# Grabber.net
KiCad netlist of a schematic drawn in Altium Designer
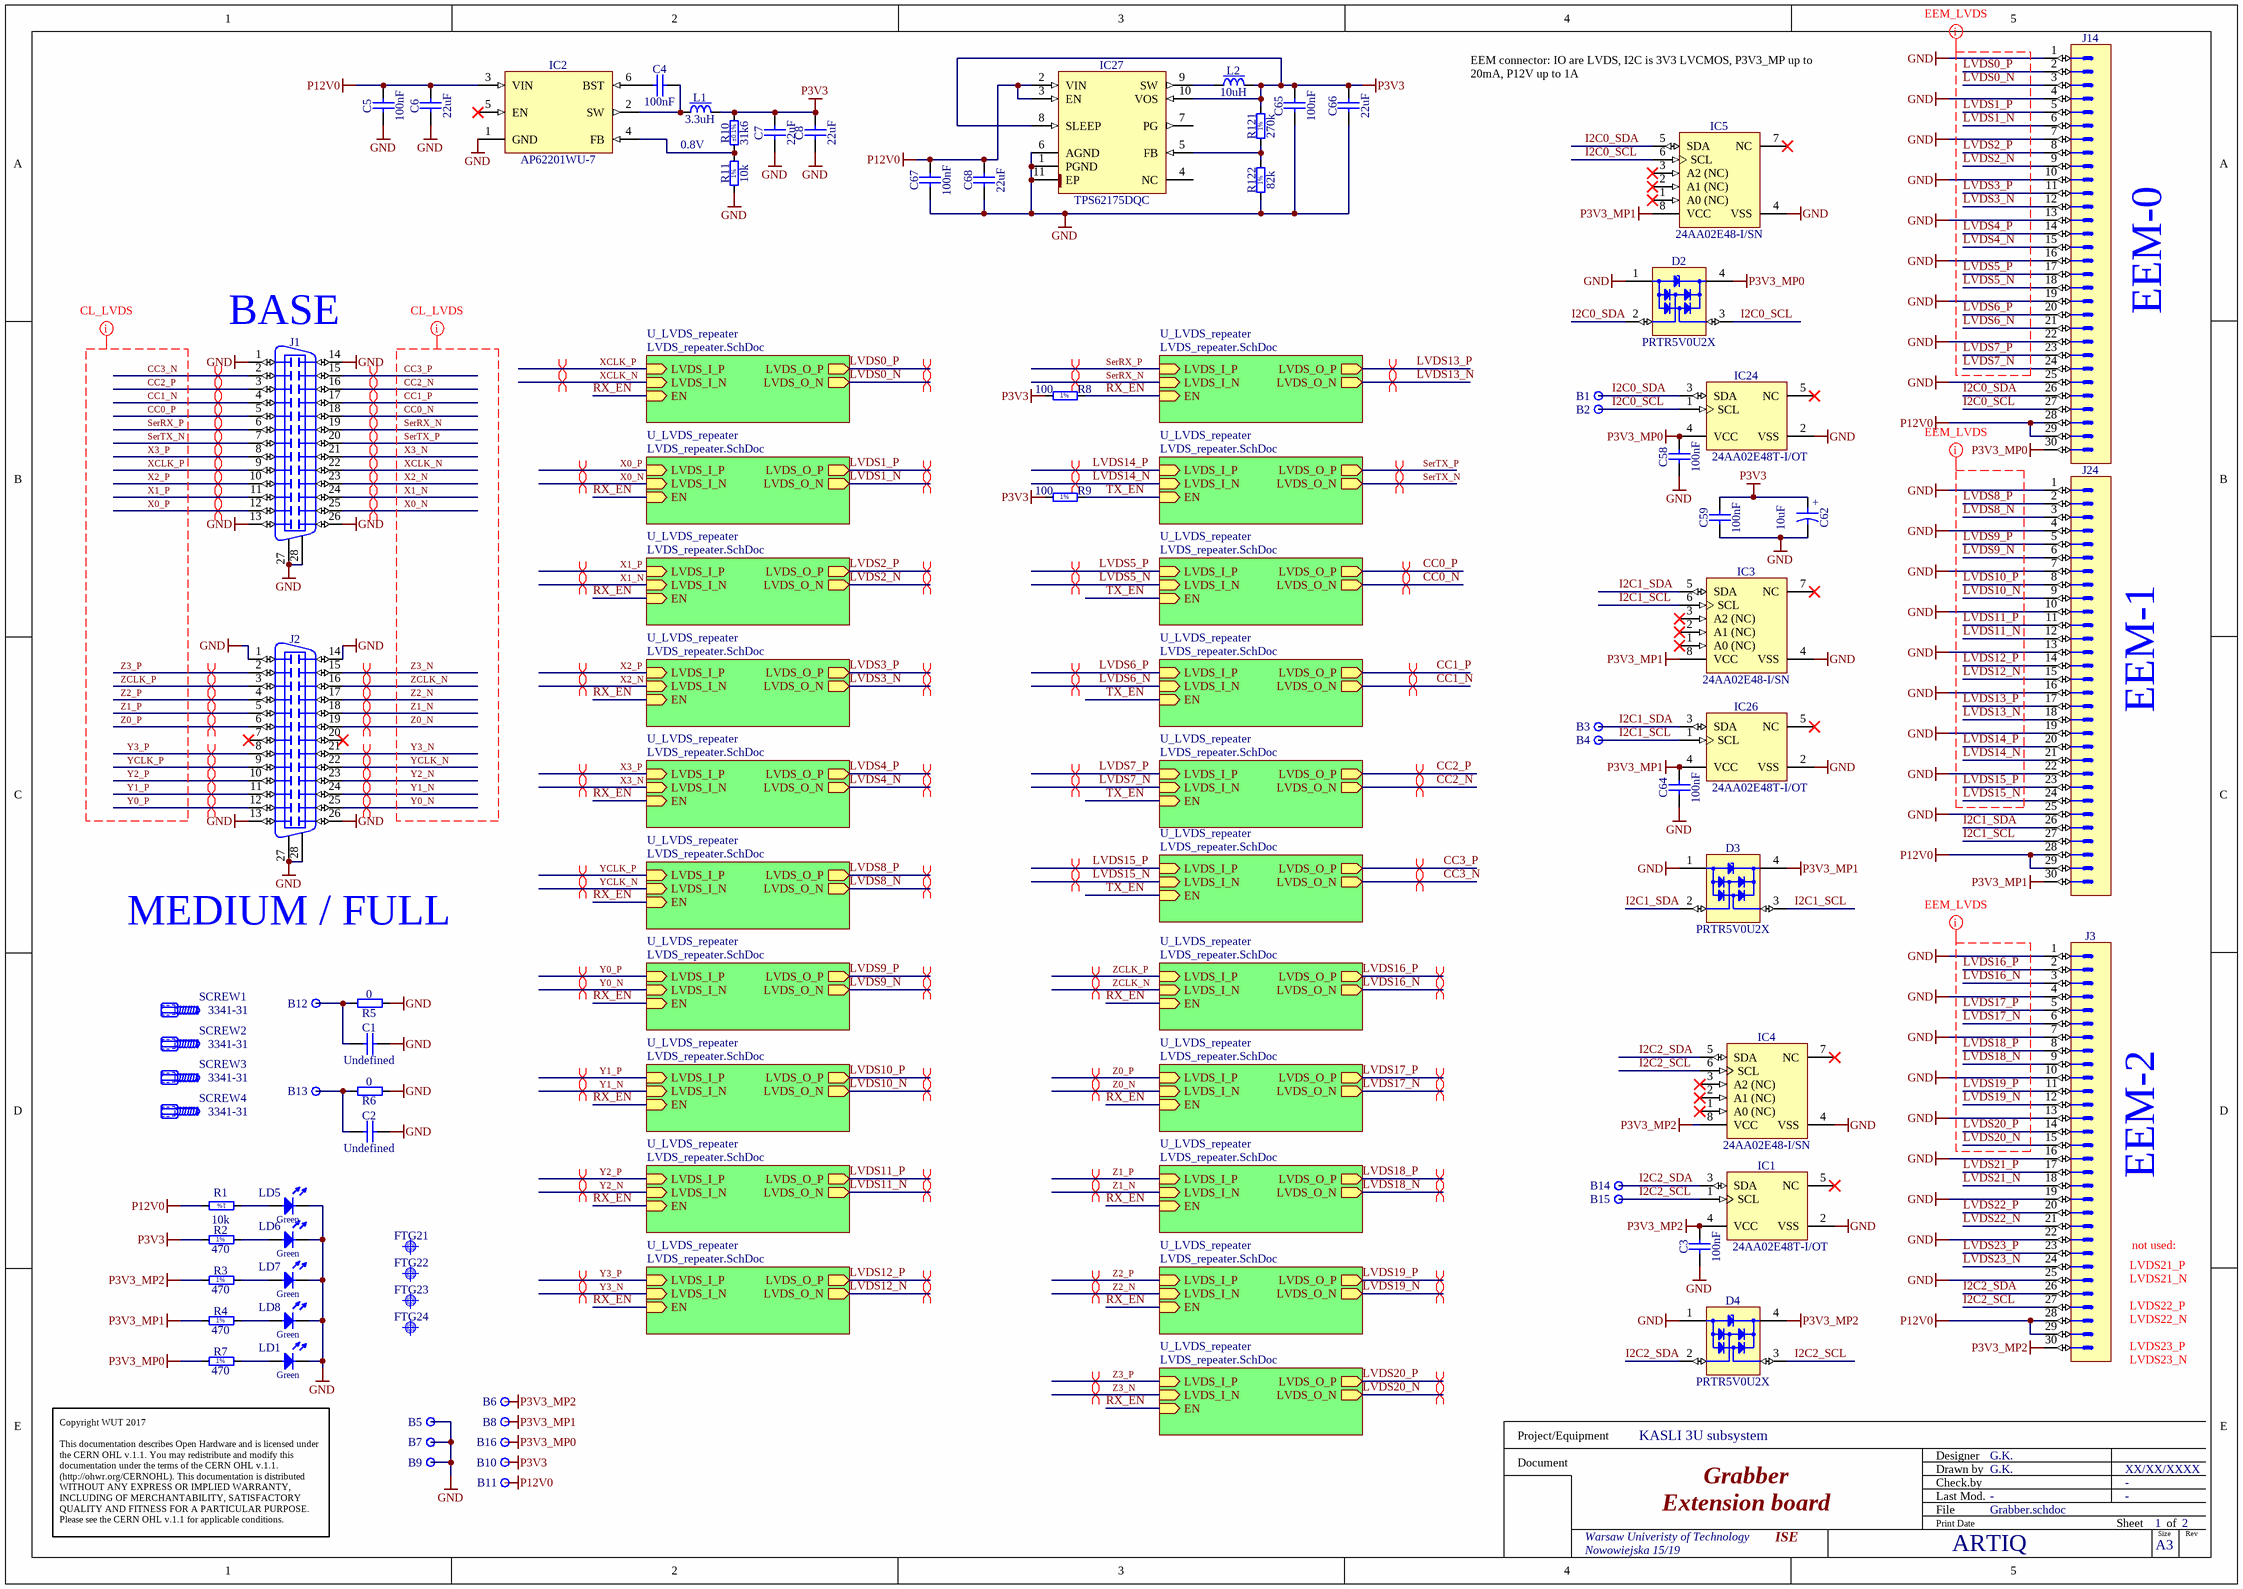
[diagram p0: Grabber.schdoc]

(export (version "E")
  (design (tool "Eeschema 10.0.6"))
  (components
    (comp (ref "B1")
      (value "Plated Hole")
      (footprint "c130h60")
      (description "Single Terminal Socket")
      (fields (field (name "PART NUMBER") "PLATED_HOLE0.6_PAD1.3"))
      (libsource (lib "Eletro-mechanical") (part "Single Terminal Socket"))
    )
    (comp (ref "B2")
      (value "Plated Hole")
      (footprint "c130h60")
      (description "Single Terminal Socket")
      (fields (field (name "PART NUMBER") "PLATED_HOLE0.6_PAD1.3"))
      (libsource (lib "Eletro-mechanical") (part "Single Terminal Socket"))
    )
    (comp (ref "B3")
      (value "Plated Hole")
      (footprint "c130h60")
      (description "Single Terminal Socket")
      (fields (field (name "PART NUMBER") "PLATED_HOLE0.6_PAD1.3"))
      (libsource (lib "Eletro-mechanical") (part "Single Terminal Socket"))
    )
    (comp (ref "B4")
      (value "Plated Hole")
      (footprint "c130h60")
      (description "Single Terminal Socket")
      (fields (field (name "PART NUMBER") "PLATED_HOLE0.6_PAD1.3"))
      (libsource (lib "Eletro-mechanical") (part "Single Terminal Socket"))
    )
    (comp (ref "B5")
      (value "Plated Hole")
      (footprint "c130h60")
      (description "Single Terminal Socket")
      (fields (field (name "PART NUMBER") "PLATED_HOLE0.6_PAD1.3"))
      (libsource (lib "Eletro-mechanical") (part "Single Terminal Socket"))
    )
    (comp (ref "B6")
      (value "Plated Hole")
      (footprint "c130h60")
      (description "Single Terminal Socket")
      (fields (field (name "PART NUMBER") "PLATED_HOLE0.6_PAD1.3"))
      (libsource (lib "Eletro-mechanical") (part "Single Terminal Socket"))
    )
    (comp (ref "B7")
      (value "Plated Hole")
      (footprint "c130h60")
      (description "Single Terminal Socket")
      (fields (field (name "PART NUMBER") "PLATED_HOLE0.6_PAD1.3"))
      (libsource (lib "Eletro-mechanical") (part "Single Terminal Socket"))
    )
    (comp (ref "B8")
      (value "Plated Hole")
      (footprint "c130h60")
      (description "Single Terminal Socket")
      (fields (field (name "PART NUMBER") "PLATED_HOLE0.6_PAD1.3"))
      (libsource (lib "Eletro-mechanical") (part "Single Terminal Socket"))
    )
    (comp (ref "B9")
      (value "Plated Hole")
      (footprint "c130h60")
      (description "Single Terminal Socket")
      (fields (field (name "PART NUMBER") "PLATED_HOLE0.6_PAD1.3"))
      (libsource (lib "Eletro-mechanical") (part "Single Terminal Socket"))
    )
    (comp (ref "B10")
      (value "Plated Hole")
      (footprint "c130h60")
      (description "Single Terminal Socket")
      (fields (field (name "PART NUMBER") "PLATED_HOLE0.6_PAD1.3"))
      (libsource (lib "Eletro-mechanical") (part "Single Terminal Socket"))
    )
    (comp (ref "B11")
      (value "Plated Hole")
      (footprint "c130h60")
      (description "Single Terminal Socket")
      (fields (field (name "PART NUMBER") "PLATED_HOLE0.6_PAD1.3"))
      (libsource (lib "Eletro-mechanical") (part "Single Terminal Socket"))
    )
    (comp (ref "B12")
      (value "Plated Hole")
      (footprint "MTG270_500")
      (description "Single Terminal Socket")
      (fields (field (name "PART NUMBER") "PLATED_HOLE2.7_PAD5.0"))
      (libsource (lib "Eletro-mechanical") (part "Single Terminal Socket"))
    )
    (comp (ref "B13")
      (value "Plated Hole")
      (footprint "MTG270_500")
      (description "Single Terminal Socket")
      (fields (field (name "PART NUMBER") "PLATED_HOLE2.7_PAD5.0"))
      (libsource (lib "Eletro-mechanical") (part "Single Terminal Socket"))
    )
    (comp (ref "B14")
      (value "Plated Hole")
      (footprint "c130h60")
      (description "Single Terminal Socket")
      (fields (field (name "PART NUMBER") "PLATED_HOLE0.6_PAD1.3"))
      (libsource (lib "Eletro-mechanical") (part "Single Terminal Socket"))
    )
    (comp (ref "B15")
      (value "Plated Hole")
      (footprint "c130h60")
      (description "Single Terminal Socket")
      (fields (field (name "PART NUMBER") "PLATED_HOLE0.6_PAD1.3"))
      (libsource (lib "Eletro-mechanical") (part "Single Terminal Socket"))
    )
    (comp (ref "B16")
      (value "Plated Hole")
      (footprint "c130h60")
      (description "Single Terminal Socket")
      (fields (field (name "PART NUMBER") "PLATED_HOLE0.6_PAD1.3"))
      (libsource (lib "Eletro-mechanical") (part "Single Terminal Socket"))
    )
    (comp (ref "C1")
      (value "Undefined")
      (footprint "CAPC2012X135N")
      (description "Non-polarised capacitor")
      (fields (field (name "PART NUMBER") "CC0805_NO-VALUE"))
      (libsource (lib "Capacitors") (part "Capacitor - non polarized"))
    )
    (comp (ref "C2")
      (value "Undefined")
      (footprint "CAPC2012X135N")
      (description "Non-polarised capacitor")
      (fields (field (name "PART NUMBER") "CC0805_NO-VALUE"))
      (libsource (lib "Capacitors") (part "Capacitor - non polarized"))
    )
    (comp (ref "C3")
      (value "100nF")
      (footprint "CAPC1005X55N")
      (description "Non-polarised capacitor")
      (fields (field (name "PART NUMBER") "CC0402_100NF_16V_10%_X5R") (field (name "VOLTAGE") "16V"))
      (libsource (lib "Capacitors") (part "Capacitor - non polarized"))
    )
    (comp (ref "C4")
      (value "100nF")
      (footprint "CAPC1005X55N")
      (description "Non-polarised capacitor")
      (fields (field (name "PART NUMBER") "CC0402_100NF_16V_10%_X5R") (field (name "VOLTAGE") "16V"))
      (libsource (lib "Capacitors") (part "Capacitor - non polarized"))
    )
    (comp (ref "C5")
      (value "100nF")
      (footprint "CAPC1005X55N")
      (description "Non-polarised capacitor")
      (fields (field (name "PART NUMBER") "CC0402_100NF_16V_10%_X5R") (field (name "VOLTAGE") "16V"))
      (libsource (lib "Capacitors") (part "Capacitor - non polarized"))
    )
    (comp (ref "C6")
      (value "22uF")
      (footprint "CAPC2012X135N")
      (description "Non-polarised capacitor")
      (fields (field (name "PART NUMBER") "CC0805_22UF_16V_10%_X5R") (field (name "VOLTAGE") "16V"))
      (libsource (lib "Capacitors") (part "Capacitor - non polarized"))
    )
    (comp (ref "C7")
      (value "22uF")
      (footprint "CAPC2012X135N")
      (description "Non-polarised capacitor")
      (fields (field (name "PART NUMBER") "CC0805_22UF_16V_10%_X5R") (field (name "VOLTAGE") "16V"))
      (libsource (lib "Capacitors") (part "Capacitor - non polarized"))
    )
    (comp (ref "C8")
      (value "22uF")
      (footprint "CAPC2012X135N")
      (description "Non-polarised capacitor")
      (fields (field (name "PART NUMBER") "CC0805_22UF_16V_10%_X5R") (field (name "VOLTAGE") "16V"))
      (libsource (lib "Capacitors") (part "Capacitor - non polarized"))
    )
    (comp (ref "C58")
      (value "100nF")
      (footprint "CAPC1005X55N")
      (description "Non-polarised capacitor")
      (fields (field (name "PART NUMBER") "CC0402_100NF_16V_10%_X5R") (field (name "VOLTAGE") "16V"))
      (libsource (lib "Capacitors") (part "Capacitor - non polarized"))
    )
    (comp (ref "C59")
      (value "100nF")
      (footprint "CAPC1005X55N")
      (description "Non-polarised capacitor")
      (fields (field (name "PART NUMBER") "CC0402_100NF_16V_10%_X5R") (field (name "VOLTAGE") "16V"))
      (libsource (lib "Capacitors") (part "Capacitor - non polarized"))
    )
    (comp (ref "C62")
      (value "10uF")
      (footprint "CAPAE430X540N")
      (description "Polarised capacitor")
      (fields (field (name "PART NUMBER") "CAE430-540_10UF_16V_20%") (field (name "VOLTAGE") "16V"))
      (libsource (lib "Capacitors") (part "Capacitor - polarized"))
    )
    (comp (ref "C64")
      (value "100nF")
      (footprint "CAPC1005X55N")
      (description "Non-polarised capacitor")
      (fields (field (name "PART NUMBER") "CC0402_100NF_16V_10%_X5R") (field (name "VOLTAGE") "16V"))
      (libsource (lib "Capacitors") (part "Capacitor - non polarized"))
    )
    (comp (ref "C65")
      (value "100nF")
      (footprint "CAPC1005X55N")
      (description "Non-polarised capacitor")
      (fields (field (name "PART NUMBER") "CC0402_100NF_16V_10%_X5R") (field (name "VOLTAGE") "16V"))
      (libsource (lib "Capacitors") (part "Capacitor - non polarized"))
    )
    (comp (ref "C66")
      (value "22uF")
      (footprint "CAPC2012X135N")
      (description "Non-polarised capacitor")
      (fields (field (name "PART NUMBER") "CC0805_22UF_16V_10%_X5R") (field (name "VOLTAGE") "16V"))
      (libsource (lib "Capacitors") (part "Capacitor - non polarized"))
    )
    (comp (ref "C67")
      (value "100nF")
      (footprint "CAPC1005X55N")
      (description "Non-polarised capacitor")
      (fields (field (name "PART NUMBER") "CC0402_100NF_16V_10%_X5R") (field (name "VOLTAGE") "16V"))
      (libsource (lib "Capacitors") (part "Capacitor - non polarized"))
    )
    (comp (ref "C68")
      (value "22uF")
      (footprint "CAPC2012X135N")
      (description "Non-polarised capacitor")
      (fields (field (name "PART NUMBER") "CC0805_22UF_16V_10%_X5R") (field (name "VOLTAGE") "16V"))
      (libsource (lib "Capacitors") (part "Capacitor - non polarized"))
    )
    (comp (ref "D2")
      (value "PRTR5V0U2X")
      (footprint "SOT190P230X110-4N")
      (description "Ultra Low Capacitance Double Rail-to-Rail ESD Protection Diode")
      (fields (field (name "VOLTAGE") "5.5V") (field (name "MANUFACTURER") "NXP SEMICONDUCTORS"))
      (libsource (lib "ICs And Semiconductors") (part "PRTR5V0U2X"))
    )
    (comp (ref "D3")
      (value "PRTR5V0U2X")
      (footprint "SOT190P230X110-4N")
      (description "Ultra Low Capacitance Double Rail-to-Rail ESD Protection Diode")
      (fields (field (name "VOLTAGE") "5.5V") (field (name "MANUFACTURER") "NXP SEMICONDUCTORS"))
      (libsource (lib "ICs And Semiconductors") (part "PRTR5V0U2X"))
    )
    (comp (ref "D4")
      (value "PRTR5V0U2X")
      (footprint "SOT190P230X110-4N")
      (description "Ultra Low Capacitance Double Rail-to-Rail ESD Protection Diode")
      (fields (field (name "VOLTAGE") "5.5V") (field (name "MANUFACTURER") "NXP SEMICONDUCTORS"))
      (libsource (lib "ICs And Semiconductors") (part "PRTR5V0U2X"))
    )
    (comp (ref "FTG21")
      (value "Use only in PCB")
      (footprint "FIDUCIAL_TOP_C100-200")
      (description "Fiducial Target")
      (fields (field (name "PART NUMBER") "FIDUCIAL_TARGET_C100-200"))
      (libsource (lib "Eletro-mechanical") (part "Fiducial Target"))
    )
    (comp (ref "FTG22")
      (value "Use only in PCB")
      (footprint "FIDUCIAL_TOP_S100-200")
      (description "Fiducial Target")
      (fields (field (name "PART NUMBER") "FIDUCIAL_TARGET_S100-200"))
      (libsource (lib "Eletro-mechanical") (part "Fiducial Target"))
    )
    (comp (ref "FTG23")
      (value "Use only in PCB")
      (footprint "FIDUCIAL_TOP_S200-400")
      (description "Fiducial Target")
      (fields (field (name "PART NUMBER") "FIDUCIAL_TARGET_S200-400"))
      (libsource (lib "Eletro-mechanical") (part "Fiducial Target"))
    )
    (comp (ref "FTG24")
      (value "Use only in PCB")
      (footprint "FIDUCIAL_TOP_S100-200")
      (description "Fiducial Target")
      (fields (field (name "PART NUMBER") "FIDUCIAL_TARGET_S100-200"))
      (libsource (lib "Eletro-mechanical") (part "Fiducial Target"))
    )
    (comp (ref "IC1")
      (value "24AA02E48T-I/OT")
      (footprint "SOT95P280X145-5N")
      (description "1.7V-5.5V, 2K I2C Serial EEPROM With EUI-48 Node Identity")
      (fields (field (name "MANUFACTURER") "MICROCHIP TECHNOLOGY"))
      (libsource (lib "ICs And Semiconductors") (part "24AA02E48T-I/OT"))
    )
    (comp (ref "IC2")
      (value "AP62201WU-7")
      (footprint "SOT95P280X100-6N")
      (description "4.2V TO 18V INPUT, 2A LOW IQ SYNCHRONOUS BUCK CONVERTER")
      (fields (field (name "MANUFACTURER") "DIODES INCORPORATED"))
      (libsource (lib "ICs And Semiconductors") (part "AP62201WU"))
    )
    (comp (ref "IC3")
      (value "24AA02E48-I/SN")
      (footprint "SOIC127P600X175-8N")
      (description "1.7V-5.5V, 2K I2C™ Serial EEPROMs with EUI-48™ Node Identity")
      (fields (field (name "MANUFACTURER") "MICROCHIP TECHNOLOGY"))
      (libsource (lib "ICS-logic") (part "MEM_24AA02E48-I/SN"))
    )
    (comp (ref "IC4")
      (value "24AA02E48-I/SN")
      (footprint "SOIC127P600X175-8N")
      (description "1.7V-5.5V, 2K I2C™ Serial EEPROMs with EUI-48™ Node Identity")
      (fields (field (name "MANUFACTURER") "MICROCHIP TECHNOLOGY"))
      (libsource (lib "ICS-logic") (part "MEM_24AA02E48-I/SN"))
    )
    (comp (ref "IC5")
      (value "24AA02E48-I/SN")
      (footprint "SOIC127P600X175-8N")
      (description "1.7V-5.5V, 2K I2C™ Serial EEPROMs with EUI-48™ Node Identity")
      (fields (field (name "MANUFACTURER") "MICROCHIP TECHNOLOGY"))
      (libsource (lib "ICS-logic") (part "MEM_24AA02E48-I/SN"))
    )
    (comp (ref "IC24")
      (value "24AA02E48T-I/OT")
      (footprint "SOT95P280X145-5N")
      (description "1.7V-5.5V, 2K I2C Serial EEPROM With EUI-48 Node Identity")
      (fields (field (name "MANUFACTURER") "MICROCHIP TECHNOLOGY"))
      (libsource (lib "ICs And Semiconductors") (part "24AA02E48T-I/OT"))
    )
    (comp (ref "IC26")
      (value "24AA02E48T-I/OT")
      (footprint "SOT95P280X145-5N")
      (description "1.7V-5.5V, 2K I2C Serial EEPROM With EUI-48 Node Identity")
      (fields (field (name "MANUFACTURER") "MICROCHIP TECHNOLOGY"))
      (libsource (lib "ICs And Semiconductors") (part "24AA02E48T-I/OT"))
    )
    (comp (ref "IC27")
      (value "TPS62175DQC")
      (footprint "SON50P200X300X80-11N-R94X250")
      (description "4.75-28VDC to 1-6VDC, 500mA Step-Down Converter With Sleep Mode")
      (fields (field (name "MANUFACTURER") "TEXAS INSTRUMENTS"))
      (libsource (lib "ICs And Semiconductors") (part "TPS62175"))
    )
    (comp (ref "J1")
      (value "MDR 26")
      (footprint "3M_N10226-5212PC")
      (description "Connector Mini D Ribbon (MDR) 26 Female")
      (fields (field (name "PART NUMBER") "3M_N10226-5212PC") (field (name "MANUFACTURER") "3M"))
      (libsource (lib "Connectors") (part "Connector MDR 26 Female"))
    )
    (comp (ref "J2")
      (value "MDR 26")
      (footprint "3M_N10226-5212PC")
      (description "Connector Mini D Ribbon (MDR) 26 Female")
      (fields (field (name "PART NUMBER") "3M_N10226-5212PC") (field (name "MANUFACTURER") "3M"))
      (libsource (lib "Connectors") (part "Connector MDR 26 Female"))
    )
    (comp (ref "J3")
      (value "~")
      (footprint "3M_N2530-6002RB")
      (description "Connector 30 Male")
      (fields (field (name "PART NUMBER") "3M_N2530-6002RB") (field (name "MANUFACTURER") "3M"))
      (libsource (lib "Connectors") (part "Connector 30 Male"))
    )
    (comp (ref "J14")
      (value "~")
      (footprint "3M_N2530-6002RB")
      (description "Connector 30 Male")
      (fields (field (name "PART NUMBER") "3M_N2530-6002RB") (field (name "MANUFACTURER") "3M"))
      (libsource (lib "Connectors") (part "Connector 30 Male"))
    )
    (comp (ref "J24")
      (value "~")
      (footprint "3M_N2530-6002RB")
      (description "Connector 30 Male")
      (fields (field (name "PART NUMBER") "3M_N2530-6002RB") (field (name "MANUFACTURER") "3M"))
      (libsource (lib "Connectors") (part "Connector 30 Male"))
    )
    (comp (ref "L1")
      (value "3.3uH")
      (footprint "IND_WURTH_WE-TPC_4828")
      (description "Inductor With Core")
      (fields
        (field (name "PART NUMBER") "IND_3.3UH_30%_WURTH_WE-TPC_744043003")
        (field (name "POWER") "2.15A")
      )
      (libsource (lib "Inductors & Transformers") (part "Inductor With Magnetic core"))
    )
    (comp (ref "L2")
      (value "10uH")
      (footprint "IND_MURATA-PS_8400")
      (description "Inductor With Core")
      (fields (field (name "PART NUMBER") "IND_10UH_10%_MURATA-PS_8400") (field (name "POWER") "950mA"))
      (libsource (lib "Inductors & Transformers") (part "Inductor With Magnetic core"))
    )
    (comp (ref "LD1")
      (value "Green")
      (footprint "LED_KINGBRIGHT_KPH-1608CGCK")
      (description "LED Green 1C 2A")
      (fields
        (field (name "PART NUMBER") "LED_KINGBRIGHT_KPH-1608CGCK")
        (field (name "MANUFACTURER") "KINGBRIGHT")
      )
      (libsource (lib "ICs And Semiconductors") (part "LED Green 1C 2A"))
    )
    (comp (ref "LD5")
      (value "Green")
      (footprint "LED_KINGBRIGHT_KPH-1608CGCK")
      (description "LED Green 1C 2A")
      (fields
        (field (name "PART NUMBER") "LED_KINGBRIGHT_KPH-1608CGCK")
        (field (name "MANUFACTURER") "KINGBRIGHT")
      )
      (libsource (lib "ICs And Semiconductors") (part "LED Green 1C 2A"))
    )
    (comp (ref "LD6")
      (value "Green")
      (footprint "LED_KINGBRIGHT_KPH-1608CGCK")
      (description "LED Green 1C 2A")
      (fields
        (field (name "PART NUMBER") "LED_KINGBRIGHT_KPH-1608CGCK")
        (field (name "MANUFACTURER") "KINGBRIGHT")
      )
      (libsource (lib "ICs And Semiconductors") (part "LED Green 1C 2A"))
    )
    (comp (ref "LD7")
      (value "Green")
      (footprint "LED_KINGBRIGHT_KPH-1608CGCK")
      (description "LED Green 1C 2A")
      (fields
        (field (name "PART NUMBER") "LED_KINGBRIGHT_KPH-1608CGCK")
        (field (name "MANUFACTURER") "KINGBRIGHT")
      )
      (libsource (lib "ICs And Semiconductors") (part "LED Green 1C 2A"))
    )
    (comp (ref "LD8")
      (value "Green")
      (footprint "LED_KINGBRIGHT_KPH-1608CGCK")
      (description "LED Green 1C 2A")
      (fields
        (field (name "PART NUMBER") "LED_KINGBRIGHT_KPH-1608CGCK")
        (field (name "MANUFACTURER") "KINGBRIGHT")
      )
      (libsource (lib "ICs And Semiconductors") (part "LED Green 1C 2A"))
    )
    (comp (ref "R1")
      (value "10k")
      (footprint "RESC1005X40N")
      (description "Resistor - 1%")
      (fields (field (name "PART NUMBER") "R0402_10K_1%_0.0625W_100PPM") (field (name "POWER") "0.0625W"))
      (libsource (lib "Resistors") (part "Resistor - 1%"))
    )
    (comp (ref "R2")
      (value "470")
      (footprint "RESC1005X40N")
      (description "Resistor - 1%")
      (fields (field (name "PART NUMBER") "R0402_470R_1%_0.0625W_100PPM") (field (name "POWER") "0.0625W"))
      (libsource (lib "Resistors") (part "Resistor - 1%"))
    )
    (comp (ref "R3")
      (value "470")
      (footprint "RESC1005X40N")
      (description "Resistor - 1%")
      (fields (field (name "PART NUMBER") "R0402_470R_1%_0.0625W_100PPM") (field (name "POWER") "0.0625W"))
      (libsource (lib "Resistors") (part "Resistor - 1%"))
    )
    (comp (ref "R4")
      (value "470")
      (footprint "RESC1005X40N")
      (description "Resistor - 1%")
      (fields (field (name "PART NUMBER") "R0402_470R_1%_0.0625W_100PPM") (field (name "POWER") "0.0625W"))
      (libsource (lib "Resistors") (part "Resistor - 1%"))
    )
    (comp (ref "R5")
      (value "0")
      (footprint "RESC1608X55N")
      (description "Resistor")
      (fields (field (name "PART NUMBER") "R0603_0R_JUMPER") (field (name "MANUFACTURER") "GENERIC"))
      (libsource (lib "Resistors") (part "Resistor"))
    )
    (comp (ref "R6")
      (value "0")
      (footprint "RESC1608X55N")
      (description "Resistor")
      (fields (field (name "PART NUMBER") "R0603_0R_JUMPER") (field (name "MANUFACTURER") "GENERIC"))
      (libsource (lib "Resistors") (part "Resistor"))
    )
    (comp (ref "R7")
      (value "470")
      (footprint "RESC1005X40N")
      (description "Resistor - 1%")
      (fields (field (name "PART NUMBER") "R0402_470R_1%_0.0625W_100PPM") (field (name "POWER") "0.0625W"))
      (libsource (lib "Resistors") (part "Resistor - 1%"))
    )
    (comp (ref "R8")
      (value "100")
      (footprint "RESC1005X40N")
      (description "Resistor - 1%")
      (fields (field (name "PART NUMBER") "R0402_100R_1%_0.1W_100PPM") (field (name "POWER") "0.1W"))
      (libsource (lib "Resistors") (part "Resistor - 1%"))
    )
    (comp (ref "R9")
      (value "100")
      (footprint "RESC1005X40N")
      (description "Resistor - 1%")
      (fields (field (name "PART NUMBER") "R0402_100R_1%_0.1W_100PPM") (field (name "POWER") "0.1W"))
      (libsource (lib "Resistors") (part "Resistor - 1%"))
    )
    (comp (ref "R10")
      (value "31k6")
      (footprint "RESC1005X35N")
      (description "Resistor - 0.1%")
      (fields
        (field (name "TOLERANCE") "±0.1%")
        (field (name "PART NUMBER") "R0402_31K6_0.1%_0.063W_25PPM_YAGEO_RT")
        (field (name "POWER") "0.063W")
      )
      (libsource (lib "Resistors") (part "Resistor - 0.1%"))
    )
    (comp (ref "R11")
      (value "10k")
      (footprint "RESC1005X40N")
      (description "Resistor - 1%")
      (fields (field (name "PART NUMBER") "R0402_10K_1%_0.0625W_100PPM") (field (name "POWER") "0.0625W"))
      (libsource (lib "Resistors") (part "Resistor - 1%"))
    )
    (comp (ref "R121")
      (value "270k")
      (footprint "RESC1608X55N")
      (description "Resistor - 1%")
      (fields (field (name "PART NUMBER") "R0603_270K_1%_0.1W_100PPM") (field (name "POWER") "0.1W"))
      (libsource (lib "Resistors") (part "Resistor - 1%"))
    )
    (comp (ref "R122")
      (value "82k")
      (footprint "RESC1608X55N")
      (description "Resistor - 1%")
      (fields (field (name "PART NUMBER") "R0603_82K_1%_0.1W_100PPM") (field (name "POWER") "0.1W"))
      (libsource (lib "Resistors") (part "Resistor - 1%"))
    )
    (comp (ref "SCREW1")
      (value "3341-31")
      (footprint "3M_3341-31")
      (description "VHDCI Female Screw Lock")
      (fields (field (name "PART NUMBER") "3M_3341-31") (field (name "MANUFACTURER") "3M"))
      (libsource (lib "LIBRARY_SCH") (part "MECH_MDR_screw_lock"))
    )
    (comp (ref "SCREW2")
      (value "3341-31")
      (footprint "3M_3341-31")
      (description "VHDCI Female Screw Lock")
      (fields (field (name "PART NUMBER") "3M_3341-31") (field (name "MANUFACTURER") "3M"))
      (libsource (lib "LIBRARY_SCH") (part "MECH_MDR_screw_lock"))
    )
    (comp (ref "SCREW3")
      (value "3341-31")
      (footprint "3M_3341-31")
      (description "VHDCI Female Screw Lock")
      (fields (field (name "PART NUMBER") "3M_3341-31") (field (name "MANUFACTURER") "3M"))
      (libsource (lib "LIBRARY_SCH") (part "MECH_MDR_screw_lock"))
    )
    (comp (ref "SCREW4")
      (value "3341-31")
      (footprint "3M_3341-31")
      (description "VHDCI Female Screw Lock")
      (fields (field (name "PART NUMBER") "3M_3341-31") (field (name "MANUFACTURER") "3M"))
      (libsource (lib "LIBRARY_SCH") (part "MECH_MDR_screw_lock"))
    )
  )
  (nets
    (net (code "1") (name "/CC0_N") (class "Default")
      (node (ref "J1") (pin "18") (pinfunction "18_18") (pintype "bidirectional"))
    )
    (net (code "2") (name "/CC0_P") (class "Default")
      (node (ref "J1") (pin "5") (pinfunction "5_5") (pintype "bidirectional"))
    )
    (net (code "3") (name "/CC1_N") (class "Default")
      (node (ref "J1") (pin "4") (pinfunction "4_4") (pintype "bidirectional"))
    )
    (net (code "4") (name "/CC1_P") (class "Default")
      (node (ref "J1") (pin "17") (pinfunction "17_17") (pintype "bidirectional"))
    )
    (net (code "5") (name "/CC2_N") (class "Default")
      (node (ref "J1") (pin "16") (pinfunction "16_16") (pintype "bidirectional"))
    )
    (net (code "6") (name "/CC2_P") (class "Default")
      (node (ref "J1") (pin "3") (pinfunction "3_3") (pintype "bidirectional"))
    )
    (net (code "7") (name "/CC3_N") (class "Default")
      (node (ref "J1") (pin "2") (pinfunction "2_2") (pintype "bidirectional"))
    )
    (net (code "8") (name "/CC3_P") (class "Default")
      (node (ref "J1") (pin "15") (pinfunction "15_15") (pintype "bidirectional"))
    )
    (net (code "9") (name "/I2C0_SCL") (class "Default")
      (node (ref "B2") (pin "1") (pinfunction "1_1") (pintype "bidirectional"))
      (node (ref "D2") (pin "3") (pinfunction "I/O2_3") (pintype "bidirectional"))
      (node (ref "IC24") (pin "1") (pinfunction "SCL_1") (pintype "input"))
      (node (ref "IC5") (pin "6") (pinfunction "SCL_6") (pintype "input"))
      (node (ref "J14") (pin "27") (pinfunction "27_27") (pintype "bidirectional"))
    )
    (net (code "10") (name "/I2C0_SDA") (class "Default")
      (node (ref "B1") (pin "1") (pinfunction "1_1") (pintype "bidirectional"))
      (node (ref "D2") (pin "2") (pinfunction "I/O1_2") (pintype "bidirectional"))
      (node (ref "IC24") (pin "3") (pinfunction "SDA_3") (pintype "bidirectional"))
      (node (ref "IC5") (pin "5") (pinfunction "SDA_5") (pintype "bidirectional"))
      (node (ref "J14") (pin "26") (pinfunction "26_26") (pintype "bidirectional"))
    )
    (net (code "11") (name "/I2C1_SCL") (class "Default")
      (node (ref "B4") (pin "1") (pinfunction "1_1") (pintype "bidirectional"))
      (node (ref "D3") (pin "3") (pinfunction "I/O2_3") (pintype "bidirectional"))
      (node (ref "IC26") (pin "1") (pinfunction "SCL_1") (pintype "input"))
      (node (ref "IC3") (pin "6") (pinfunction "SCL_6") (pintype "input"))
      (node (ref "J24") (pin "27") (pinfunction "27_27") (pintype "bidirectional"))
    )
    (net (code "12") (name "/I2C1_SDA") (class "Default")
      (node (ref "B3") (pin "1") (pinfunction "1_1") (pintype "bidirectional"))
      (node (ref "D3") (pin "2") (pinfunction "I/O1_2") (pintype "bidirectional"))
      (node (ref "IC26") (pin "3") (pinfunction "SDA_3") (pintype "bidirectional"))
      (node (ref "IC3") (pin "5") (pinfunction "SDA_5") (pintype "bidirectional"))
      (node (ref "J24") (pin "26") (pinfunction "26_26") (pintype "bidirectional"))
    )
    (net (code "13") (name "/I2C2_SCL") (class "Default")
      (node (ref "B15") (pin "1") (pinfunction "1_1") (pintype "bidirectional"))
      (node (ref "D4") (pin "3") (pinfunction "I/O2_3") (pintype "bidirectional"))
      (node (ref "IC1") (pin "1") (pinfunction "SCL_1") (pintype "input"))
      (node (ref "IC4") (pin "6") (pinfunction "SCL_6") (pintype "input"))
      (node (ref "J3") (pin "27") (pinfunction "27_27") (pintype "bidirectional"))
    )
    (net (code "14") (name "/I2C2_SDA") (class "Default")
      (node (ref "B14") (pin "1") (pinfunction "1_1") (pintype "bidirectional"))
      (node (ref "D4") (pin "2") (pinfunction "I/O1_2") (pintype "bidirectional"))
      (node (ref "IC1") (pin "3") (pinfunction "SDA_3") (pintype "bidirectional"))
      (node (ref "IC4") (pin "5") (pinfunction "SDA_5") (pintype "bidirectional"))
      (node (ref "J3") (pin "26") (pinfunction "26_26") (pintype "bidirectional"))
    )
    (net (code "15") (name "/LVDS0_N") (class "Default")
      (node (ref "J14") (pin "3") (pinfunction "3_3") (pintype "bidirectional"))
    )
    (net (code "16") (name "/LVDS0_P") (class "Default")
      (node (ref "J14") (pin "2") (pinfunction "2_2") (pintype "bidirectional"))
    )
    (net (code "17") (name "/LVDS1_N") (class "Default")
      (node (ref "J14") (pin "6") (pinfunction "6_6") (pintype "bidirectional"))
    )
    (net (code "18") (name "/LVDS1_P") (class "Default")
      (node (ref "J14") (pin "5") (pinfunction "5_5") (pintype "bidirectional"))
    )
    (net (code "19") (name "/LVDS2_N") (class "Default")
      (node (ref "J14") (pin "9") (pinfunction "9_9") (pintype "bidirectional"))
    )
    (net (code "20") (name "/LVDS2_P") (class "Default")
      (node (ref "J14") (pin "8") (pinfunction "8_8") (pintype "bidirectional"))
    )
    (net (code "21") (name "/LVDS3_N") (class "Default")
      (node (ref "J14") (pin "12") (pinfunction "12_12") (pintype "bidirectional"))
    )
    (net (code "22") (name "/LVDS3_P") (class "Default")
      (node (ref "J14") (pin "11") (pinfunction "11_11") (pintype "bidirectional"))
    )
    (net (code "23") (name "/LVDS4_N") (class "Default")
      (node (ref "J14") (pin "15") (pinfunction "15_15") (pintype "bidirectional"))
    )
    (net (code "24") (name "/LVDS4_P") (class "Default")
      (node (ref "J14") (pin "14") (pinfunction "14_14") (pintype "bidirectional"))
    )
    (net (code "25") (name "/LVDS5_N") (class "Default")
      (node (ref "J14") (pin "18") (pinfunction "18_18") (pintype "bidirectional"))
    )
    (net (code "26") (name "/LVDS5_P") (class "Default")
      (node (ref "J14") (pin "17") (pinfunction "17_17") (pintype "bidirectional"))
    )
    (net (code "27") (name "/LVDS6_N") (class "Default")
      (node (ref "J14") (pin "21") (pinfunction "21_21") (pintype "bidirectional"))
    )
    (net (code "28") (name "/LVDS6_P") (class "Default")
      (node (ref "J14") (pin "20") (pinfunction "20_20") (pintype "bidirectional"))
    )
    (net (code "29") (name "/LVDS7_N") (class "Default")
      (node (ref "J14") (pin "24") (pinfunction "24_24") (pintype "bidirectional"))
    )
    (net (code "30") (name "/LVDS7_P") (class "Default")
      (node (ref "J14") (pin "23") (pinfunction "23_23") (pintype "bidirectional"))
    )
    (net (code "31") (name "/LVDS8_N") (class "Default")
      (node (ref "J24") (pin "3") (pinfunction "3_3") (pintype "bidirectional"))
    )
    (net (code "32") (name "/LVDS8_P") (class "Default")
      (node (ref "J24") (pin "2") (pinfunction "2_2") (pintype "bidirectional"))
    )
    (net (code "33") (name "/LVDS9_N") (class "Default")
      (node (ref "J24") (pin "6") (pinfunction "6_6") (pintype "bidirectional"))
    )
    (net (code "34") (name "/LVDS9_P") (class "Default")
      (node (ref "J24") (pin "5") (pinfunction "5_5") (pintype "bidirectional"))
    )
    (net (code "35") (name "/LVDS10_N") (class "Default")
      (node (ref "J24") (pin "9") (pinfunction "9_9") (pintype "bidirectional"))
    )
    (net (code "36") (name "/LVDS10_P") (class "Default")
      (node (ref "J24") (pin "8") (pinfunction "8_8") (pintype "bidirectional"))
    )
    (net (code "37") (name "/LVDS11_N") (class "Default")
      (node (ref "J24") (pin "12") (pinfunction "12_12") (pintype "bidirectional"))
    )
    (net (code "38") (name "/LVDS11_P") (class "Default")
      (node (ref "J24") (pin "11") (pinfunction "11_11") (pintype "bidirectional"))
    )
    (net (code "39") (name "/LVDS12_N") (class "Default")
      (node (ref "J24") (pin "15") (pinfunction "15_15") (pintype "bidirectional"))
    )
    (net (code "40") (name "/LVDS12_P") (class "Default")
      (node (ref "J24") (pin "14") (pinfunction "14_14") (pintype "bidirectional"))
    )
    (net (code "41") (name "/LVDS13_N") (class "Default")
      (node (ref "J24") (pin "18") (pinfunction "18_18") (pintype "bidirectional"))
    )
    (net (code "42") (name "/LVDS13_P") (class "Default")
      (node (ref "J24") (pin "17") (pinfunction "17_17") (pintype "bidirectional"))
    )
    (net (code "43") (name "/LVDS14_N") (class "Default")
      (node (ref "J24") (pin "21") (pinfunction "21_21") (pintype "bidirectional"))
    )
    (net (code "44") (name "/LVDS14_P") (class "Default")
      (node (ref "J24") (pin "20") (pinfunction "20_20") (pintype "bidirectional"))
    )
    (net (code "45") (name "/LVDS15_N") (class "Default")
      (node (ref "J24") (pin "24") (pinfunction "24_24") (pintype "bidirectional"))
    )
    (net (code "46") (name "/LVDS15_P") (class "Default")
      (node (ref "J24") (pin "23") (pinfunction "23_23") (pintype "bidirectional"))
    )
    (net (code "47") (name "/LVDS16_N") (class "Default")
      (node (ref "J3") (pin "3") (pinfunction "3_3") (pintype "bidirectional"))
    )
    (net (code "48") (name "/LVDS16_P") (class "Default")
      (node (ref "J3") (pin "2") (pinfunction "2_2") (pintype "bidirectional"))
    )
    (net (code "49") (name "/LVDS17_N") (class "Default")
      (node (ref "J3") (pin "6") (pinfunction "6_6") (pintype "bidirectional"))
    )
    (net (code "50") (name "/LVDS17_P") (class "Default")
      (node (ref "J3") (pin "5") (pinfunction "5_5") (pintype "bidirectional"))
    )
    (net (code "51") (name "/LVDS18_N") (class "Default")
      (node (ref "J3") (pin "9") (pinfunction "9_9") (pintype "bidirectional"))
    )
    (net (code "52") (name "/LVDS18_P") (class "Default")
      (node (ref "J3") (pin "8") (pinfunction "8_8") (pintype "bidirectional"))
    )
    (net (code "53") (name "/LVDS19_N") (class "Default")
      (node (ref "J3") (pin "12") (pinfunction "12_12") (pintype "bidirectional"))
    )
    (net (code "54") (name "/LVDS19_P") (class "Default")
      (node (ref "J3") (pin "11") (pinfunction "11_11") (pintype "bidirectional"))
    )
    (net (code "55") (name "/LVDS20_N") (class "Default")
      (node (ref "J3") (pin "15") (pinfunction "15_15") (pintype "bidirectional"))
    )
    (net (code "56") (name "/LVDS20_P") (class "Default")
      (node (ref "J3") (pin "14") (pinfunction "14_14") (pintype "bidirectional"))
    )
    (net (code "57") (name "/LVDS21_N") (class "Default")
      (node (ref "J3") (pin "18") (pinfunction "18_18") (pintype "bidirectional"))
    )
    (net (code "58") (name "/LVDS21_P") (class "Default")
      (node (ref "J3") (pin "17") (pinfunction "17_17") (pintype "bidirectional"))
    )
    (net (code "59") (name "/LVDS22_N") (class "Default")
      (node (ref "J3") (pin "21") (pinfunction "21_21") (pintype "bidirectional"))
    )
    (net (code "60") (name "/LVDS22_P") (class "Default")
      (node (ref "J3") (pin "20") (pinfunction "20_20") (pintype "bidirectional"))
    )
    (net (code "61") (name "/LVDS23_N") (class "Default")
      (node (ref "J3") (pin "24") (pinfunction "24_24") (pintype "bidirectional"))
    )
    (net (code "62") (name "/LVDS23_P") (class "Default")
      (node (ref "J3") (pin "23") (pinfunction "23_23") (pintype "bidirectional"))
    )
    (net (code "63") (name "/RX_EN") (class "Default")
      (node (ref "R8") (pin "2") (pinfunction "2_2") (pintype "passive"))
    )
    (net (code "64") (name "/SerRX_N") (class "Default")
      (node (ref "J1") (pin "19") (pinfunction "19_19") (pintype "bidirectional"))
    )
    (net (code "65") (name "/SerRX_P") (class "Default")
      (node (ref "J1") (pin "6") (pinfunction "6_6") (pintype "bidirectional"))
    )
    (net (code "66") (name "/SerTX_N") (class "Default")
      (node (ref "J1") (pin "7") (pinfunction "7_7") (pintype "bidirectional"))
    )
    (net (code "67") (name "/SerTX_P") (class "Default")
      (node (ref "J1") (pin "20") (pinfunction "20_20") (pintype "bidirectional"))
    )
    (net (code "68") (name "/TX_EN") (class "Default")
      (node (ref "R9") (pin "2") (pinfunction "2_2") (pintype "passive"))
    )
    (net (code "69") (name "/X0_N") (class "Default")
      (node (ref "J1") (pin "25") (pinfunction "25_25") (pintype "bidirectional"))
    )
    (net (code "70") (name "/X0_P") (class "Default")
      (node (ref "J1") (pin "12") (pinfunction "12_12") (pintype "bidirectional"))
    )
    (net (code "71") (name "/X1_N") (class "Default")
      (node (ref "J1") (pin "24") (pinfunction "24_24") (pintype "bidirectional"))
    )
    (net (code "72") (name "/X1_P") (class "Default")
      (node (ref "J1") (pin "11") (pinfunction "11_11") (pintype "bidirectional"))
    )
    (net (code "73") (name "/X2_N") (class "Default")
      (node (ref "J1") (pin "23") (pinfunction "23_23") (pintype "bidirectional"))
    )
    (net (code "74") (name "/X2_P") (class "Default")
      (node (ref "J1") (pin "10") (pinfunction "10_10") (pintype "bidirectional"))
    )
    (net (code "75") (name "/X3_N") (class "Default")
      (node (ref "J1") (pin "21") (pinfunction "21_21") (pintype "bidirectional"))
    )
    (net (code "76") (name "/X3_P") (class "Default")
      (node (ref "J1") (pin "8") (pinfunction "8_8") (pintype "bidirectional"))
    )
    (net (code "77") (name "/XCLK_N") (class "Default")
      (node (ref "J1") (pin "22") (pinfunction "22_22") (pintype "bidirectional"))
    )
    (net (code "78") (name "/XCLK_P") (class "Default")
      (node (ref "J1") (pin "9") (pinfunction "9_9") (pintype "bidirectional"))
    )
    (net (code "79") (name "/Y0_N") (class "Default")
      (node (ref "J2") (pin "25") (pinfunction "25_25") (pintype "bidirectional"))
    )
    (net (code "80") (name "/Y0_P") (class "Default")
      (node (ref "J2") (pin "12") (pinfunction "12_12") (pintype "bidirectional"))
    )
    (net (code "81") (name "/Y1_N") (class "Default")
      (node (ref "J2") (pin "24") (pinfunction "24_24") (pintype "bidirectional"))
    )
    (net (code "82") (name "/Y1_P") (class "Default")
      (node (ref "J2") (pin "11") (pinfunction "11_11") (pintype "bidirectional"))
    )
    (net (code "83") (name "/Y2_N") (class "Default")
      (node (ref "J2") (pin "23") (pinfunction "23_23") (pintype "bidirectional"))
    )
    (net (code "84") (name "/Y2_P") (class "Default")
      (node (ref "J2") (pin "10") (pinfunction "10_10") (pintype "bidirectional"))
    )
    (net (code "85") (name "/Y3_N") (class "Default")
      (node (ref "J2") (pin "21") (pinfunction "21_21") (pintype "bidirectional"))
    )
    (net (code "86") (name "/Y3_P") (class "Default")
      (node (ref "J2") (pin "8") (pinfunction "8_8") (pintype "bidirectional"))
    )
    (net (code "87") (name "/YCLK_N") (class "Default")
      (node (ref "J2") (pin "22") (pinfunction "22_22") (pintype "bidirectional"))
    )
    (net (code "88") (name "/YCLK_P") (class "Default")
      (node (ref "J2") (pin "9") (pinfunction "9_9") (pintype "bidirectional"))
    )
    (net (code "89") (name "/Z0_N") (class "Default")
      (node (ref "J2") (pin "19") (pinfunction "19_19") (pintype "bidirectional"))
    )
    (net (code "90") (name "/Z0_P") (class "Default")
      (node (ref "J2") (pin "6") (pinfunction "6_6") (pintype "bidirectional"))
    )
    (net (code "91") (name "/Z1_N") (class "Default")
      (node (ref "J2") (pin "18") (pinfunction "18_18") (pintype "bidirectional"))
    )
    (net (code "92") (name "/Z1_P") (class "Default")
      (node (ref "J2") (pin "5") (pinfunction "5_5") (pintype "bidirectional"))
    )
    (net (code "93") (name "/Z2_N") (class "Default")
      (node (ref "J2") (pin "17") (pinfunction "17_17") (pintype "bidirectional"))
    )
    (net (code "94") (name "/Z2_P") (class "Default")
      (node (ref "J2") (pin "4") (pinfunction "4_4") (pintype "bidirectional"))
    )
    (net (code "95") (name "/Z3_N") (class "Default")
      (node (ref "J2") (pin "15") (pinfunction "15_15") (pintype "bidirectional"))
    )
    (net (code "96") (name "/Z3_P") (class "Default")
      (node (ref "J2") (pin "2") (pinfunction "2_2") (pintype "bidirectional"))
    )
    (net (code "97") (name "/ZCLK_N") (class "Default")
      (node (ref "J2") (pin "16") (pinfunction "16_16") (pintype "bidirectional"))
    )
    (net (code "98") (name "/ZCLK_P") (class "Default")
      (node (ref "J2") (pin "3") (pinfunction "3_3") (pintype "bidirectional"))
    )
    (net (code "99") (name "GND") (class "Default")
      (node (ref "B5") (pin "1") (pinfunction "1_1") (pintype "bidirectional"))
      (node (ref "B7") (pin "1") (pinfunction "1_1") (pintype "bidirectional"))
      (node (ref "B9") (pin "1") (pinfunction "1_1") (pintype "bidirectional"))
      (node (ref "C1") (pin "2") (pinfunction "2_2") (pintype "passive"))
      (node (ref "C2") (pin "2") (pinfunction "2_2") (pintype "passive"))
      (node (ref "C3") (pin "1") (pinfunction "1_1") (pintype "passive"))
      (node (ref "C5") (pin "1") (pinfunction "1_1") (pintype "passive"))
      (node (ref "C58") (pin "1") (pinfunction "1_1") (pintype "passive"))
      (node (ref "C59") (pin "1") (pinfunction "1_1") (pintype "passive"))
      (node (ref "C6") (pin "1") (pinfunction "1_1") (pintype "passive"))
      (node (ref "C62") (pin "2") (pinfunction "2_2") (pintype "passive"))
      (node (ref "C64") (pin "1") (pinfunction "1_1") (pintype "passive"))
      (node (ref "C65") (pin "1") (pinfunction "1_1") (pintype "passive"))
      (node (ref "C66") (pin "1") (pinfunction "1_1") (pintype "passive"))
      (node (ref "C67") (pin "1") (pinfunction "1_1") (pintype "passive"))
      (node (ref "C68") (pin "1") (pinfunction "1_1") (pintype "passive"))
      (node (ref "C7") (pin "1") (pinfunction "1_1") (pintype "passive"))
      (node (ref "C8") (pin "1") (pinfunction "1_1") (pintype "passive"))
      (node (ref "D2") (pin "1") (pinfunction "GND_1") (pintype "power_in"))
      (node (ref "D3") (pin "1") (pinfunction "GND_1") (pintype "power_in"))
      (node (ref "D4") (pin "1") (pinfunction "GND_1") (pintype "power_in"))
      (node (ref "IC1") (pin "2") (pinfunction "VSS_2") (pintype "power_in"))
      (node (ref "IC2") (pin "1") (pinfunction "GND_1") (pintype "power_in"))
      (node (ref "IC24") (pin "2") (pinfunction "VSS_2") (pintype "power_in"))
      (node (ref "IC26") (pin "2") (pinfunction "VSS_2") (pintype "power_in"))
      (node (ref "IC27") (pin "1") (pinfunction "PGND_1") (pintype "power_in"))
      (node (ref "IC27") (pin "11") (pinfunction "EP_11") (pintype "power_in"))
      (node (ref "IC27") (pin "6") (pinfunction "AGND_6") (pintype "power_in"))
      (node (ref "IC3") (pin "4") (pinfunction "VSS_4") (pintype "power_in"))
      (node (ref "IC4") (pin "4") (pinfunction "VSS_4") (pintype "power_in"))
      (node (ref "IC5") (pin "4") (pinfunction "VSS_4") (pintype "power_in"))
      (node (ref "J1") (pin "1") (pinfunction "1_1") (pintype "bidirectional"))
      (node (ref "J1") (pin "13") (pinfunction "13_13") (pintype "bidirectional"))
      (node (ref "J1") (pin "14") (pinfunction "14_14") (pintype "bidirectional"))
      (node (ref "J1") (pin "26") (pinfunction "26_26") (pintype "bidirectional"))
      (node (ref "J1") (pin "27") (pinfunction "27_27") (pintype "passive"))
      (node (ref "J1") (pin "28") (pinfunction "28_28") (pintype "passive"))
      (node (ref "J14") (pin "1") (pinfunction "1_1") (pintype "bidirectional"))
      (node (ref "J14") (pin "10") (pinfunction "10_10") (pintype "bidirectional"))
      (node (ref "J14") (pin "13") (pinfunction "13_13") (pintype "bidirectional"))
      (node (ref "J14") (pin "16") (pinfunction "16_16") (pintype "bidirectional"))
      (node (ref "J14") (pin "19") (pinfunction "19_19") (pintype "bidirectional"))
      (node (ref "J14") (pin "22") (pinfunction "22_22") (pintype "bidirectional"))
      (node (ref "J14") (pin "25") (pinfunction "25_25") (pintype "bidirectional"))
      (node (ref "J14") (pin "4") (pinfunction "4_4") (pintype "bidirectional"))
      (node (ref "J14") (pin "7") (pinfunction "7_7") (pintype "bidirectional"))
      (node (ref "J2") (pin "1") (pinfunction "1_1") (pintype "bidirectional"))
      (node (ref "J2") (pin "13") (pinfunction "13_13") (pintype "bidirectional"))
      (node (ref "J2") (pin "14") (pinfunction "14_14") (pintype "bidirectional"))
      (node (ref "J2") (pin "26") (pinfunction "26_26") (pintype "bidirectional"))
      (node (ref "J2") (pin "27") (pinfunction "27_27") (pintype "passive"))
      (node (ref "J2") (pin "28") (pinfunction "28_28") (pintype "passive"))
      (node (ref "J24") (pin "1") (pinfunction "1_1") (pintype "bidirectional"))
      (node (ref "J24") (pin "10") (pinfunction "10_10") (pintype "bidirectional"))
      (node (ref "J24") (pin "13") (pinfunction "13_13") (pintype "bidirectional"))
      (node (ref "J24") (pin "16") (pinfunction "16_16") (pintype "bidirectional"))
      (node (ref "J24") (pin "19") (pinfunction "19_19") (pintype "bidirectional"))
      (node (ref "J24") (pin "22") (pinfunction "22_22") (pintype "bidirectional"))
      (node (ref "J24") (pin "25") (pinfunction "25_25") (pintype "bidirectional"))
      (node (ref "J24") (pin "4") (pinfunction "4_4") (pintype "bidirectional"))
      (node (ref "J24") (pin "7") (pinfunction "7_7") (pintype "bidirectional"))
      (node (ref "J3") (pin "1") (pinfunction "1_1") (pintype "bidirectional"))
      (node (ref "J3") (pin "10") (pinfunction "10_10") (pintype "bidirectional"))
      (node (ref "J3") (pin "13") (pinfunction "13_13") (pintype "bidirectional"))
      (node (ref "J3") (pin "16") (pinfunction "16_16") (pintype "bidirectional"))
      (node (ref "J3") (pin "19") (pinfunction "19_19") (pintype "bidirectional"))
      (node (ref "J3") (pin "22") (pinfunction "22_22") (pintype "bidirectional"))
      (node (ref "J3") (pin "25") (pinfunction "25_25") (pintype "bidirectional"))
      (node (ref "J3") (pin "4") (pinfunction "4_4") (pintype "bidirectional"))
      (node (ref "J3") (pin "7") (pinfunction "7_7") (pintype "bidirectional"))
      (node (ref "LD1") (pin "1") (pinfunction "C_1") (pintype "passive"))
      (node (ref "LD5") (pin "1") (pinfunction "C_1") (pintype "passive"))
      (node (ref "LD6") (pin "1") (pinfunction "C_1") (pintype "passive"))
      (node (ref "LD7") (pin "1") (pinfunction "C_1") (pintype "passive"))
      (node (ref "LD8") (pin "1") (pinfunction "C_1") (pintype "passive"))
      (node (ref "R11") (pin "1") (pinfunction "1_1") (pintype "passive"))
      (node (ref "R122") (pin "1") (pinfunction "1_1") (pintype "passive"))
      (node (ref "R5") (pin "1") (pinfunction "1_1") (pintype "passive"))
      (node (ref "R6") (pin "1") (pinfunction "1_1") (pintype "passive"))
    )
    (net (code "100") (name "Net-(B12-Pad1)") (class "Default")
      (node (ref "B12") (pin "1") (pinfunction "1_1") (pintype "bidirectional"))
      (node (ref "C1") (pin "1") (pinfunction "1_1") (pintype "passive"))
      (node (ref "R5") (pin "2") (pinfunction "2_2") (pintype "passive"))
    )
    (net (code "101") (name "Net-(B13-Pad1)") (class "Default")
      (node (ref "B13") (pin "1") (pinfunction "1_1") (pintype "bidirectional"))
      (node (ref "C2") (pin "1") (pinfunction "1_1") (pintype "passive"))
      (node (ref "R6") (pin "2") (pinfunction "2_2") (pintype "passive"))
    )
    (net (code "102") (name "Net-(IC2-BST)") (class "Default")
      (node (ref "C4") (pin "1") (pinfunction "1_1") (pintype "passive"))
      (node (ref "IC2") (pin "6") (pinfunction "BST_6") (pintype "input"))
    )
    (net (code "103") (name "Net-(IC2-FB)") (class "Default")
      (node (ref "IC2") (pin "4") (pinfunction "FB_4") (pintype "input"))
      (node (ref "R10") (pin "1") (pinfunction "1_1") (pintype "passive"))
      (node (ref "R11") (pin "2") (pinfunction "2_2") (pintype "passive"))
    )
    (net (code "104") (name "Net-(IC2-SW)") (class "Default")
      (node (ref "C4") (pin "2") (pinfunction "2_2") (pintype "passive"))
      (node (ref "IC2") (pin "2") (pinfunction "SW_2") (pintype "output"))
      (node (ref "L1") (pin "1") (pinfunction "1_1") (pintype "passive"))
    )
    (net (code "105") (name "Net-(IC27-FB)") (class "Default")
      (node (ref "IC27") (pin "5") (pinfunction "FB_5") (pintype "input"))
      (node (ref "R121") (pin "1") (pinfunction "1_1") (pintype "passive"))
      (node (ref "R122") (pin "2") (pinfunction "2_2") (pintype "passive"))
    )
    (net (code "106") (name "Net-(IC27-SW)") (class "Default")
      (node (ref "IC27") (pin "9") (pinfunction "SW_9") (pintype "output"))
      (node (ref "L2") (pin "1") (pinfunction "1_1") (pintype "passive"))
    )
    (net (code "107") (name "Net-(LD1-A)") (class "Default")
      (node (ref "LD1") (pin "2") (pinfunction "A_2") (pintype "passive"))
      (node (ref "R7") (pin "2") (pinfunction "2_2") (pintype "passive"))
    )
    (net (code "108") (name "Net-(LD5-A)") (class "Default")
      (node (ref "LD5") (pin "2") (pinfunction "A_2") (pintype "passive"))
      (node (ref "R1") (pin "1") (pinfunction "1_1") (pintype "passive"))
    )
    (net (code "109") (name "Net-(LD6-A)") (class "Default")
      (node (ref "LD6") (pin "2") (pinfunction "A_2") (pintype "passive"))
      (node (ref "R2") (pin "2") (pinfunction "2_2") (pintype "passive"))
    )
    (net (code "110") (name "Net-(LD7-A)") (class "Default")
      (node (ref "LD7") (pin "2") (pinfunction "A_2") (pintype "passive"))
      (node (ref "R3") (pin "2") (pinfunction "2_2") (pintype "passive"))
    )
    (net (code "111") (name "Net-(LD8-A)") (class "Default")
      (node (ref "LD8") (pin "2") (pinfunction "A_2") (pintype "passive"))
      (node (ref "R4") (pin "2") (pinfunction "2_2") (pintype "passive"))
    )
    (net (code "112") (name "P3V3") (class "Default")
      (node (ref "B10") (pin "1") (pinfunction "1_1") (pintype "bidirectional"))
      (node (ref "C59") (pin "2") (pinfunction "2_2") (pintype "passive"))
      (node (ref "C62") (pin "1") (pinfunction "1_1") (pintype "passive"))
      (node (ref "C65") (pin "2") (pinfunction "2_2") (pintype "passive"))
      (node (ref "C66") (pin "2") (pinfunction "2_2") (pintype "passive"))
      (node (ref "C7") (pin "2") (pinfunction "2_2") (pintype "passive"))
      (node (ref "C8") (pin "2") (pinfunction "2_2") (pintype "passive"))
      (node (ref "IC27") (pin "10") (pinfunction "VOS_10") (pintype "input"))
      (node (ref "IC27") (pin "8") (pinfunction "SLEEP_8") (pintype "input"))
      (node (ref "L1") (pin "2") (pinfunction "2_2") (pintype "passive"))
      (node (ref "L2") (pin "2") (pinfunction "2_2") (pintype "passive"))
      (node (ref "R10") (pin "2") (pinfunction "2_2") (pintype "passive"))
      (node (ref "R121") (pin "2") (pinfunction "2_2") (pintype "passive"))
      (node (ref "R2") (pin "1") (pinfunction "1_1") (pintype "passive"))
      (node (ref "R8") (pin "1") (pinfunction "1_1") (pintype "passive"))
      (node (ref "R9") (pin "1") (pinfunction "1_1") (pintype "passive"))
    )
    (net (code "113") (name "P3V3_MP0") (class "Default")
      (node (ref "B16") (pin "1") (pinfunction "1_1") (pintype "bidirectional"))
      (node (ref "C58") (pin "2") (pinfunction "2_2") (pintype "passive"))
      (node (ref "D2") (pin "4") (pinfunction "VCC_4") (pintype "power_in"))
      (node (ref "IC24") (pin "4") (pinfunction "VCC_4") (pintype "power_in"))
      (node (ref "J14") (pin "30") (pinfunction "30_30") (pintype "bidirectional"))
      (node (ref "R7") (pin "1") (pinfunction "1_1") (pintype "passive"))
    )
    (net (code "114") (name "P3V3_MP1") (class "Default")
      (node (ref "B8") (pin "1") (pinfunction "1_1") (pintype "bidirectional"))
      (node (ref "C64") (pin "2") (pinfunction "2_2") (pintype "passive"))
      (node (ref "D3") (pin "4") (pinfunction "VCC_4") (pintype "power_in"))
      (node (ref "IC26") (pin "4") (pinfunction "VCC_4") (pintype "power_in"))
      (node (ref "IC3") (pin "8") (pinfunction "VCC_8") (pintype "power_in"))
      (node (ref "IC5") (pin "8") (pinfunction "VCC_8") (pintype "power_in"))
      (node (ref "J24") (pin "30") (pinfunction "30_30") (pintype "bidirectional"))
      (node (ref "R4") (pin "1") (pinfunction "1_1") (pintype "passive"))
    )
    (net (code "115") (name "P3V3_MP2") (class "Default")
      (node (ref "B6") (pin "1") (pinfunction "1_1") (pintype "bidirectional"))
      (node (ref "C3") (pin "2") (pinfunction "2_2") (pintype "passive"))
      (node (ref "D4") (pin "4") (pinfunction "VCC_4") (pintype "power_in"))
      (node (ref "IC1") (pin "4") (pinfunction "VCC_4") (pintype "power_in"))
      (node (ref "IC4") (pin "8") (pinfunction "VCC_8") (pintype "power_in"))
      (node (ref "J3") (pin "30") (pinfunction "30_30") (pintype "bidirectional"))
      (node (ref "R3") (pin "1") (pinfunction "1_1") (pintype "passive"))
    )
    (net (code "116") (name "P12V0") (class "Default")
      (node (ref "B11") (pin "1") (pinfunction "1_1") (pintype "bidirectional"))
      (node (ref "C5") (pin "2") (pinfunction "2_2") (pintype "passive"))
      (node (ref "C6") (pin "2") (pinfunction "2_2") (pintype "passive"))
      (node (ref "C67") (pin "2") (pinfunction "2_2") (pintype "passive"))
      (node (ref "C68") (pin "2") (pinfunction "2_2") (pintype "passive"))
      (node (ref "IC2") (pin "3") (pinfunction "VIN_3") (pintype "input"))
      (node (ref "IC27") (pin "2") (pinfunction "VIN_2") (pintype "input"))
      (node (ref "IC27") (pin "3") (pinfunction "EN_3") (pintype "input"))
      (node (ref "J14") (pin "28") (pinfunction "28_28") (pintype "bidirectional"))
      (node (ref "J14") (pin "29") (pinfunction "29_29") (pintype "bidirectional"))
      (node (ref "J24") (pin "28") (pinfunction "28_28") (pintype "bidirectional"))
      (node (ref "J24") (pin "29") (pinfunction "29_29") (pintype "bidirectional"))
      (node (ref "J3") (pin "28") (pinfunction "28_28") (pintype "bidirectional"))
      (node (ref "J3") (pin "29") (pinfunction "29_29") (pintype "bidirectional"))
      (node (ref "R1") (pin "2") (pinfunction "2_2") (pintype "passive"))
    )
    (net (code "117") (name "unconnected-(IC1-NC-Pad5)") (class "Default")
      (node (ref "IC1") (pin "5") (pinfunction "NC_5") (pintype "passive+no_connect"))
    )
    (net (code "118") (name "unconnected-(IC2-EN-Pad5)") (class "Default")
      (node (ref "IC2") (pin "5") (pinfunction "EN_5") (pintype "input+no_connect"))
    )
    (net (code "119") (name "unconnected-(IC3-A0_(NC)-Pad1)") (class "Default")
      (node (ref "IC3") (pin "1") (pinfunction "A0_(NC)_1") (pintype "input+no_connect"))
    )
    (net (code "120") (name "unconnected-(IC3-A1_(NC)-Pad2)") (class "Default")
      (node (ref "IC3") (pin "2") (pinfunction "A1_(NC)_2") (pintype "input+no_connect"))
    )
    (net (code "121") (name "unconnected-(IC3-A2_(NC)-Pad3)") (class "Default")
      (node (ref "IC3") (pin "3") (pinfunction "A2_(NC)_3") (pintype "input+no_connect"))
    )
    (net (code "122") (name "unconnected-(IC3-NC-Pad7)") (class "Default")
      (node (ref "IC3") (pin "7") (pinfunction "NC_7") (pintype "passive+no_connect"))
    )
    (net (code "123") (name "unconnected-(IC4-A0_(NC)-Pad1)") (class "Default")
      (node (ref "IC4") (pin "1") (pinfunction "A0_(NC)_1") (pintype "input+no_connect"))
    )
    (net (code "124") (name "unconnected-(IC4-A1_(NC)-Pad2)") (class "Default")
      (node (ref "IC4") (pin "2") (pinfunction "A1_(NC)_2") (pintype "input+no_connect"))
    )
    (net (code "125") (name "unconnected-(IC4-A2_(NC)-Pad3)") (class "Default")
      (node (ref "IC4") (pin "3") (pinfunction "A2_(NC)_3") (pintype "input+no_connect"))
    )
    (net (code "126") (name "unconnected-(IC4-NC-Pad7)") (class "Default")
      (node (ref "IC4") (pin "7") (pinfunction "NC_7") (pintype "passive+no_connect"))
    )
    (net (code "127") (name "unconnected-(IC5-A0_(NC)-Pad1)") (class "Default")
      (node (ref "IC5") (pin "1") (pinfunction "A0_(NC)_1") (pintype "input+no_connect"))
    )
    (net (code "128") (name "unconnected-(IC5-A1_(NC)-Pad2)") (class "Default")
      (node (ref "IC5") (pin "2") (pinfunction "A1_(NC)_2") (pintype "input+no_connect"))
    )
    (net (code "129") (name "unconnected-(IC5-A2_(NC)-Pad3)") (class "Default")
      (node (ref "IC5") (pin "3") (pinfunction "A2_(NC)_3") (pintype "input+no_connect"))
    )
    (net (code "130") (name "unconnected-(IC5-NC-Pad7)") (class "Default")
      (node (ref "IC5") (pin "7") (pinfunction "NC_7") (pintype "passive+no_connect"))
    )
    (net (code "131") (name "unconnected-(IC24-NC-Pad5)") (class "Default")
      (node (ref "IC24") (pin "5") (pinfunction "NC_5") (pintype "passive+no_connect"))
    )
    (net (code "132") (name "unconnected-(IC26-NC-Pad5)") (class "Default")
      (node (ref "IC26") (pin "5") (pinfunction "NC_5") (pintype "passive+no_connect"))
    )
    (net (code "133") (name "unconnected-(IC27-NC-Pad4)") (class "Default")
      (node (ref "IC27") (pin "4") (pinfunction "NC_4") (pintype "passive"))
    )
    (net (code "134") (name "unconnected-(IC27-PG-Pad7)") (class "Default")
      (node (ref "IC27") (pin "7") (pinfunction "PG_7") (pintype "output"))
    )
    (net (code "135") (name "unconnected-(J2-Pad7)") (class "Default")
      (node (ref "J2") (pin "7") (pinfunction "7_7") (pintype "bidirectional+no_connect"))
    )
    (net (code "136") (name "unconnected-(J2-Pad20)") (class "Default")
      (node (ref "J2") (pin "20") (pinfunction "20_20") (pintype "bidirectional+no_connect"))
    )
  )
)
